# EVENTCTRL_DDS.net
KiCad netlist of a schematic drawn in Altium Designer
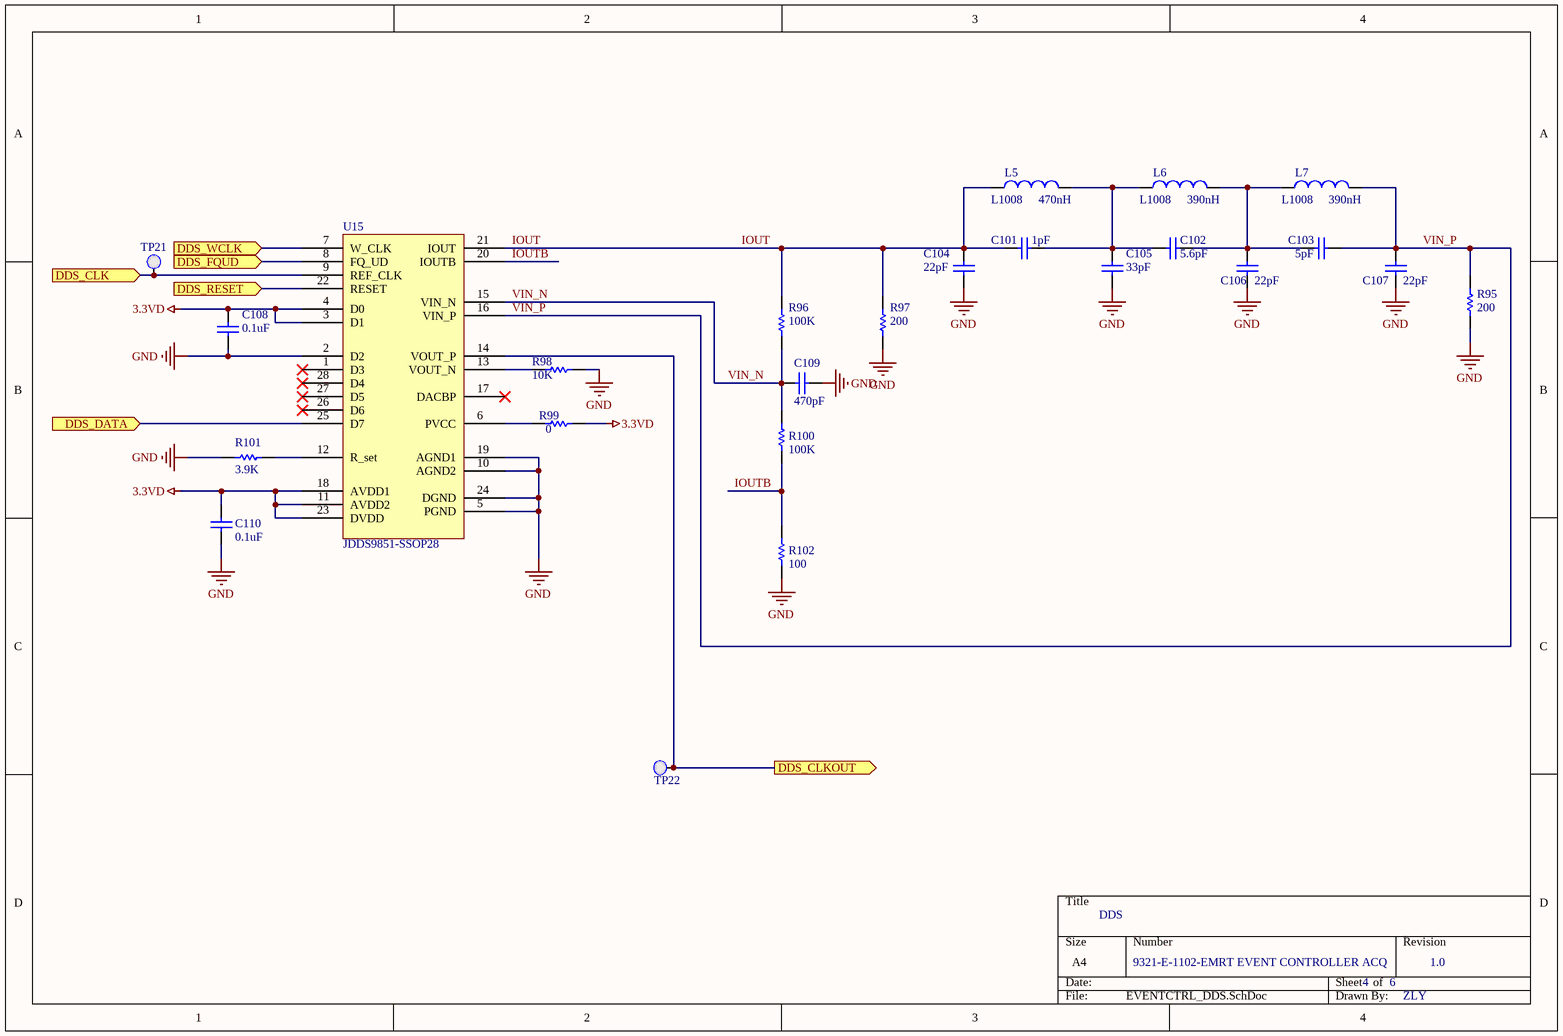
[diagram p0: EVENTCTRL_DDS.SchDoc]

(export (version "E")
  (design (tool "Eeschema 10.0.6"))
  (components
    (comp (ref "C101")
      (value "1pF")
      (footprint "0805")
      (description "Capacitor")
      (fields (field (name "Comment") "C0805"))
      (libsource (lib "Miscellaneous Devices") (part "Cap"))
    )
    (comp (ref "C102")
      (value "5.6pF")
      (footprint "0805")
      (description "Capacitor")
      (fields (field (name "Comment") "C0805"))
      (libsource (lib "Miscellaneous Devices") (part "Cap"))
    )
    (comp (ref "C103")
      (value "5pF")
      (footprint "0805")
      (description "Capacitor")
      (fields (field (name "Comment") "C0805"))
      (libsource (lib "Miscellaneous Devices") (part "Cap"))
    )
    (comp (ref "C104")
      (value "22pF")
      (footprint "0805")
      (description "Capacitor")
      (fields (field (name "Comment") "C0805"))
      (libsource (lib "Miscellaneous Devices") (part "Cap"))
    )
    (comp (ref "C105")
      (value "33pF")
      (footprint "0805")
      (description "Capacitor")
      (fields (field (name "Comment") "C0805"))
      (libsource (lib "Miscellaneous Devices") (part "Cap"))
    )
    (comp (ref "C106")
      (value "22pF")
      (footprint "0805")
      (description "Capacitor")
      (fields (field (name "Comment") "C0805"))
      (libsource (lib "Miscellaneous Devices") (part "Cap"))
    )
    (comp (ref "C107")
      (value "22pF")
      (footprint "0805")
      (description "Capacitor")
      (fields (field (name "Comment") "C0805"))
      (libsource (lib "Miscellaneous Devices") (part "Cap"))
    )
    (comp (ref "C108")
      (value "0.1uF")
      (footprint "0805")
      (description "Capacitor")
      (fields (field (name "Comment") "C0805"))
      (libsource (lib "Miscellaneous Devices") (part "Cap"))
    )
    (comp (ref "C109")
      (value "470pF")
      (footprint "0805")
      (description "Capacitor")
      (fields (field (name "Comment") "C0805"))
      (libsource (lib "Miscellaneous Devices") (part "Cap"))
    )
    (comp (ref "C110")
      (value "0.1uF")
      (footprint "0805")
      (description "Capacitor")
      (fields (field (name "Comment") "C0805"))
      (libsource (lib "Miscellaneous Devices") (part "Cap"))
    )
    (comp (ref "L5")
      (value "L1008")
      (footprint "1008")
      (description "Inductor")
      (fields (field (name "ALTIUM_VALUE") "470nH"))
      (libsource (lib "Miscellaneous Devices") (part "Inductor"))
    )
    (comp (ref "L6")
      (value "L1008")
      (footprint "1008")
      (description "Inductor")
      (fields (field (name "ALTIUM_VALUE") "390nH"))
      (libsource (lib "Miscellaneous Devices") (part "Inductor"))
    )
    (comp (ref "L7")
      (value "L1008")
      (footprint "1008")
      (description "Inductor")
      (fields (field (name "ALTIUM_VALUE") "390nH"))
      (libsource (lib "Miscellaneous Devices") (part "Inductor"))
    )
    (comp (ref "R95")
      (value "200")
      (footprint "R0805")
      (description "Resistor")
      (fields (field (name "Comment") "R0805"))
      (libsource (lib "Miscellaneous Devices") (part "Res1"))
    )
    (comp (ref "R96")
      (value "100K")
      (footprint "R0805")
      (description "Resistor")
      (fields (field (name "Comment") "R0805"))
      (libsource (lib "Miscellaneous Devices") (part "Res1"))
    )
    (comp (ref "R97")
      (value "200")
      (footprint "R0805")
      (description "Resistor")
      (fields (field (name "Comment") "R0805"))
      (libsource (lib "Miscellaneous Devices") (part "Res1"))
    )
    (comp (ref "R98")
      (value "10K")
      (footprint "R0805")
      (description "Resistor")
      (fields (field (name "Comment") "R0805"))
      (libsource (lib "Miscellaneous Devices") (part "Res1"))
    )
    (comp (ref "R99")
      (value "0")
      (footprint "R0805")
      (description "Resistor")
      (fields (field (name "Comment") "R0805"))
      (libsource (lib "Miscellaneous Devices") (part "Res1"))
    )
    (comp (ref "R100")
      (value "100K")
      (footprint "R0805")
      (description "Resistor")
      (fields (field (name "Comment") "R0805"))
      (libsource (lib "Miscellaneous Devices") (part "Res1"))
    )
    (comp (ref "R101")
      (value "3.9K")
      (footprint "R0805")
      (description "Resistor")
      (fields (field (name "Comment") "R0805"))
      (libsource (lib "Miscellaneous Devices") (part "Res1"))
    )
    (comp (ref "R102")
      (value "100")
      (footprint "R0805")
      (description "Resistor")
      (fields (field (name "Comment") "R0805"))
      (libsource (lib "Miscellaneous Devices") (part "Res1"))
    )
    (comp (ref "TP21") (value "TP") (footprint "TPA") (libsource (lib "") (part "TP_1")))
    (comp (ref "TP22") (value "TP") (footprint "TPA") (libsource (lib "*") (part "TP")))
    (comp (ref "U15") (value "JDDS9851-SSOP28") (footprint "TSSOP28") (libsource (lib "srj") (part "JS9851")))
  )
  (nets
    (net (code "1") (name "/DDS_CLK") (class "Default")
      (node (ref "TP21") (pin "1") (pinfunction "TP_1") (pintype "passive"))
      (node (ref "U15") (pin "9") (pinfunction "REF_CLK_9") (pintype "passive"))
    )
    (net (code "2") (name "/DDS_CLKOUT") (class "Default")
      (node (ref "TP22") (pin "1") (pinfunction "TP_1") (pintype "passive"))
      (node (ref "U15") (pin "14") (pinfunction "VOUT_P_14") (pintype "passive"))
    )
    (net (code "3") (name "/DDS_DATA") (class "Default")
      (node (ref "U15") (pin "25") (pinfunction "D7_25") (pintype "passive"))
    )
    (net (code "4") (name "/DDS_FQUD") (class "Default")
      (node (ref "U15") (pin "8") (pinfunction "FQ_UD_8") (pintype "passive"))
    )
    (net (code "5") (name "/DDS_RESET") (class "Default")
      (node (ref "U15") (pin "22") (pinfunction "RESET_22") (pintype "passive"))
    )
    (net (code "6") (name "/DDS_WCLK") (class "Default")
      (node (ref "U15") (pin "7") (pinfunction "W_CLK_7") (pintype "passive"))
    )
    (net (code "7") (name "/IOUT") (class "Default")
      (node (ref "C101") (pin "1") (pinfunction "1_1") (pintype "passive"))
      (node (ref "C104") (pin "2") (pinfunction "2_2") (pintype "passive"))
      (node (ref "L5") (pin "1") (pinfunction "1_1") (pintype "passive"))
      (node (ref "R96") (pin "2") (pinfunction "2_2") (pintype "passive"))
      (node (ref "R97") (pin "2") (pinfunction "2_2") (pintype "passive"))
      (node (ref "U15") (pin "21") (pinfunction "IOUT_21") (pintype "passive"))
    )
    (net (code "8") (name "/IOUTB") (class "Default")
      (node (ref "R100") (pin "1") (pinfunction "1_1") (pintype "passive"))
      (node (ref "R102") (pin "2") (pinfunction "2_2") (pintype "passive"))
      (node (ref "U15") (pin "20") (pinfunction "IOUTB_20") (pintype "passive"))
    )
    (net (code "9") (name "/VIN_N") (class "Default")
      (node (ref "C109") (pin "2") (pinfunction "2_2") (pintype "passive"))
      (node (ref "R100") (pin "2") (pinfunction "2_2") (pintype "passive"))
      (node (ref "R96") (pin "1") (pinfunction "1_1") (pintype "passive"))
      (node (ref "U15") (pin "15") (pinfunction "VIN_N_15") (pintype "passive"))
    )
    (net (code "10") (name "/VIN_P") (class "Default")
      (node (ref "C103") (pin "2") (pinfunction "2_2") (pintype "passive"))
      (node (ref "C107") (pin "2") (pinfunction "2_2") (pintype "passive"))
      (node (ref "L7") (pin "2") (pinfunction "2_2") (pintype "passive"))
      (node (ref "R95") (pin "2") (pinfunction "2_2") (pintype "passive"))
      (node (ref "U15") (pin "16") (pinfunction "VIN_P_16") (pintype "passive"))
    )
    (net (code "11") (name "3.3VD") (class "Default")
      (node (ref "C108") (pin "2") (pinfunction "2_2") (pintype "passive"))
      (node (ref "C110") (pin "2") (pinfunction "2_2") (pintype "passive"))
      (node (ref "R99") (pin "2") (pinfunction "2_2") (pintype "passive"))
      (node (ref "U15") (pin "11") (pinfunction "AVDD2_11") (pintype "passive"))
      (node (ref "U15") (pin "18") (pinfunction "AVDD1_18") (pintype "passive"))
      (node (ref "U15") (pin "23") (pinfunction "DVDD_23") (pintype "passive"))
      (node (ref "U15") (pin "3") (pinfunction "D1_3") (pintype "passive"))
      (node (ref "U15") (pin "4") (pinfunction "D0_4") (pintype "passive"))
    )
    (net (code "12") (name "GND") (class "Default")
      (node (ref "C104") (pin "1") (pinfunction "1_1") (pintype "passive"))
      (node (ref "C105") (pin "1") (pinfunction "1_1") (pintype "passive"))
      (node (ref "C106") (pin "1") (pinfunction "1_1") (pintype "passive"))
      (node (ref "C107") (pin "1") (pinfunction "1_1") (pintype "passive"))
      (node (ref "C108") (pin "1") (pinfunction "1_1") (pintype "passive"))
      (node (ref "C109") (pin "1") (pinfunction "1_1") (pintype "passive"))
      (node (ref "C110") (pin "1") (pinfunction "1_1") (pintype "passive"))
      (node (ref "R101") (pin "1") (pinfunction "1_1") (pintype "passive"))
      (node (ref "R102") (pin "1") (pinfunction "1_1") (pintype "passive"))
      (node (ref "R95") (pin "1") (pinfunction "1_1") (pintype "passive"))
      (node (ref "R97") (pin "1") (pinfunction "1_1") (pintype "passive"))
      (node (ref "R98") (pin "2") (pinfunction "2_2") (pintype "passive"))
      (node (ref "U15") (pin "10") (pinfunction "AGND2_10") (pintype "passive"))
      (node (ref "U15") (pin "19") (pinfunction "AGND1_19") (pintype "passive"))
      (node (ref "U15") (pin "2") (pinfunction "D2_2") (pintype "passive"))
      (node (ref "U15") (pin "24") (pinfunction "DGND_24") (pintype "passive"))
      (node (ref "U15") (pin "5") (pinfunction "PGND_5") (pintype "passive"))
    )
    (net (code "13") (name "Net-(C101-Pad2)") (class "Default")
      (node (ref "C101") (pin "2") (pinfunction "2_2") (pintype "passive"))
      (node (ref "C102") (pin "1") (pinfunction "1_1") (pintype "passive"))
      (node (ref "C105") (pin "2") (pinfunction "2_2") (pintype "passive"))
      (node (ref "L5") (pin "2") (pinfunction "2_2") (pintype "passive"))
      (node (ref "L6") (pin "1") (pinfunction "1_1") (pintype "passive"))
    )
    (net (code "14") (name "Net-(C102-Pad2)") (class "Default")
      (node (ref "C102") (pin "2") (pinfunction "2_2") (pintype "passive"))
      (node (ref "C103") (pin "1") (pinfunction "1_1") (pintype "passive"))
      (node (ref "C106") (pin "2") (pinfunction "2_2") (pintype "passive"))
      (node (ref "L6") (pin "2") (pinfunction "2_2") (pintype "passive"))
      (node (ref "L7") (pin "1") (pinfunction "1_1") (pintype "passive"))
    )
    (net (code "15") (name "Net-(U15-PVCC)") (class "Default")
      (node (ref "R99") (pin "1") (pinfunction "1_1") (pintype "passive"))
      (node (ref "U15") (pin "6") (pinfunction "PVCC_6") (pintype "passive"))
    )
    (net (code "16") (name "Net-(U15-R_set)") (class "Default")
      (node (ref "R101") (pin "2") (pinfunction "2_2") (pintype "passive"))
      (node (ref "U15") (pin "12") (pinfunction "R_set_12") (pintype "passive"))
    )
    (net (code "17") (name "Net-(U15-VOUT_N)") (class "Default")
      (node (ref "R98") (pin "1") (pinfunction "1_1") (pintype "passive"))
      (node (ref "U15") (pin "13") (pinfunction "VOUT_N_13") (pintype "passive"))
    )
    (net (code "18") (name "unconnected-(U15-D3-Pad1)") (class "Default")
      (node (ref "U15") (pin "1") (pinfunction "D3_1") (pintype "passive+no_connect"))
    )
    (net (code "19") (name "unconnected-(U15-D4-Pad28)") (class "Default")
      (node (ref "U15") (pin "28") (pinfunction "D4_28") (pintype "passive+no_connect"))
    )
    (net (code "20") (name "unconnected-(U15-D5-Pad27)") (class "Default")
      (node (ref "U15") (pin "27") (pinfunction "D5_27") (pintype "passive+no_connect"))
    )
    (net (code "21") (name "unconnected-(U15-D6-Pad26)") (class "Default")
      (node (ref "U15") (pin "26") (pinfunction "D6_26") (pintype "passive+no_connect"))
    )
    (net (code "22") (name "unconnected-(U15-DACBP-Pad17)") (class "Default")
      (node (ref "U15") (pin "17") (pinfunction "DACBP_17") (pintype "passive+no_connect"))
    )
  )
)
